# Sec_Controller_Sheet4.net
KiCad netlist of a schematic drawn in Altium Designer
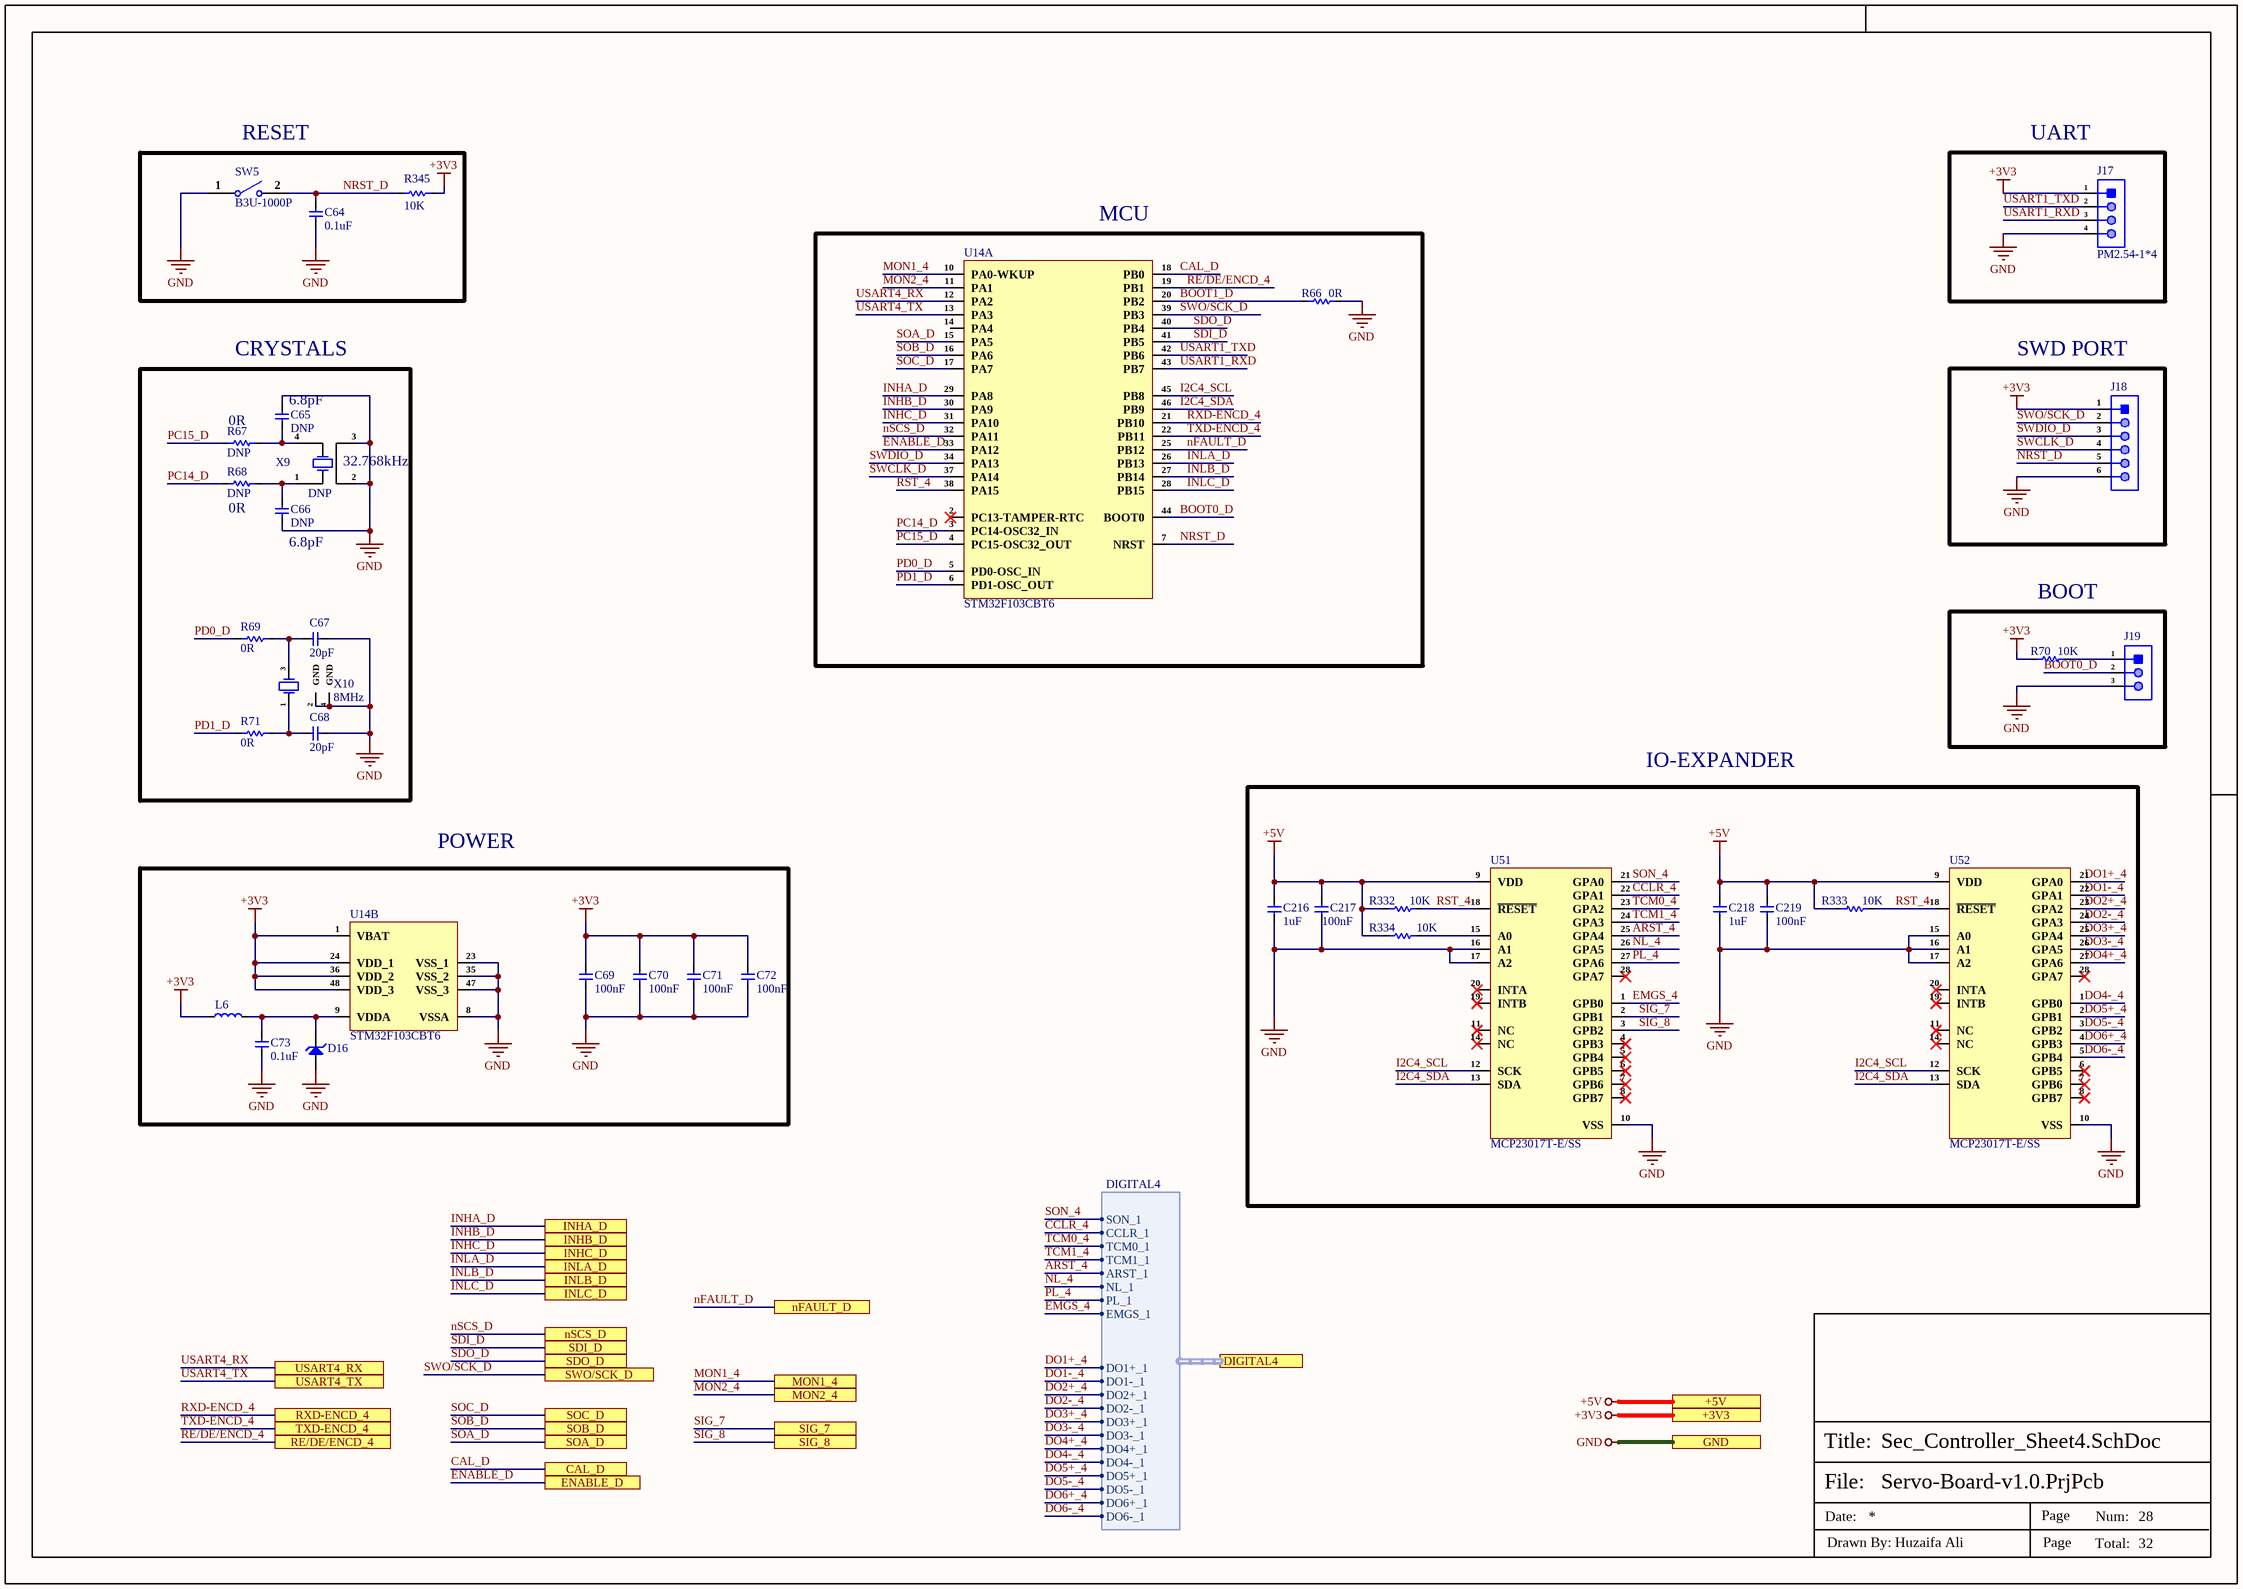
[diagram p0: Sec_Controller_Sheet4.SchDoc]

(export (version "E")
  (design (tool "Eeschema 10.0.6"))
  (components
    (comp (ref "C64")
      (value "0.1uF")
      (footprint "Cap-0402")
      (description "CAP CER 0.1UF 16V X7R 0402")
      (fields
        (field (name "MANUFACTURER") "Yageo")
        (field (name "MANUFACTURER PART NUMBER") "CC0402JRX7R7BB104")
      )
      (libsource (lib "eSpark Libraries") (part "CC0402JRX7R7BB104"))
    )
    (comp (ref "C65")
      (value "DNP")
      (footprint "Cap-0402")
      (description "CAP CER 6.8PF 50V C0G/NPO 0402")
      (fields
        (field (name "MANUFACTURER") "Yageo")
        (field (name "MANUFACTURER PART NUMBER") "CC0402CRNPO9BN6R8")
      )
      (libsource (lib "eSpark Libraries") (part "CC0402CRNPO9BN6R8"))
    )
    (comp (ref "C66")
      (value "DNP")
      (footprint "Cap-0402")
      (description "CAP CER 6.8PF 50V C0G/NPO 0402")
      (fields
        (field (name "MANUFACTURER") "Yageo")
        (field (name "MANUFACTURER PART NUMBER") "CC0402CRNPO9BN6R8")
      )
      (libsource (lib "eSpark Libraries") (part "CC0402CRNPO9BN6R8"))
    )
    (comp (ref "C67")
      (value "20pF")
      (footprint "Cap-0402")
      (description "CAP CER 20PF 50V C0G/NPO 0402")
      (fields (field (name "LCSC PART NUMBER") "C107000") (field (name "MANUFACTURER") "Yageo"))
      (libsource (lib "eSpark Libraries") (part "CC0402JRNPO9BN200"))
    )
    (comp (ref "C68")
      (value "20pF")
      (footprint "Cap-0402")
      (description "CAP CER 20PF 50V C0G/NPO 0402")
      (fields (field (name "LCSC PART NUMBER") "C107000") (field (name "MANUFACTURER") "Yageo"))
      (libsource (lib "eSpark Libraries") (part "CC0402JRNPO9BN200"))
    )
    (comp (ref "C69")
      (value "100nF")
      (footprint "cap-0402")
      (description "CAP CER 0.1UF 50V X7R 0402")
      (fields
        (field (name "MANUFACTURER") "TDK")
        (field (name "MANUFACTURER PART NUMBER") "C1005X7R1H104KT000F")
      )
      (libsource (lib "eSpark Libraries") (part "C1005X7R1H104KT000F"))
    )
    (comp (ref "C70")
      (value "100nF")
      (footprint "cap-0402")
      (description "CAP CER 0.1UF 50V X7R 0402")
      (fields
        (field (name "MANUFACTURER") "TDK")
        (field (name "MANUFACTURER PART NUMBER") "C1005X7R1H104KT000F")
      )
      (libsource (lib "eSpark Libraries") (part "C1005X7R1H104KT000F"))
    )
    (comp (ref "C71")
      (value "100nF")
      (footprint "cap-0402")
      (description "CAP CER 0.1UF 50V X7R 0402")
      (fields
        (field (name "MANUFACTURER") "TDK")
        (field (name "MANUFACTURER PART NUMBER") "C1005X7R1H104KT000F")
      )
      (libsource (lib "eSpark Libraries") (part "C1005X7R1H104KT000F"))
    )
    (comp (ref "C72")
      (value "100nF")
      (footprint "cap-0402")
      (description "CAP CER 0.1UF 50V X7R 0402")
      (fields
        (field (name "MANUFACTURER") "TDK")
        (field (name "MANUFACTURER PART NUMBER") "C1005X7R1H104KT000F")
      )
      (libsource (lib "eSpark Libraries") (part "C1005X7R1H104KT000F"))
    )
    (comp (ref "C73")
      (value "0.1uF")
      (footprint "Cap-0402")
      (description "CAP CER 0.1UF 16V X7R 0402")
      (fields
        (field (name "MANUFACTURER") "Yageo")
        (field (name "MANUFACTURER PART NUMBER") "CC0402JRX7R7BB104")
      )
      (libsource (lib "eSpark Libraries") (part "CC0402JRX7R7BB104"))
    )
    (comp (ref "C216")
      (value "1uF")
      (footprint "Cap-0402")
      (description "CAP CER 1UF 10V X5R 0402")
      (fields
        (field (name "MANUFACTURER") "Yageo")
        (field (name "MANUFACTURER PART NUMBER") "CC0402KRX5R6BB105")
      )
      (libsource (lib "eSpark Libraries") (part "CC0402KRX5R6BB105"))
    )
    (comp (ref "C217")
      (value "100nF")
      (footprint "cap-0402")
      (description "CAP CER 0.1UF 50V X7R 0402")
      (fields
        (field (name "MANUFACTURER") "TDK")
        (field (name "MANUFACTURER PART NUMBER") "C1005X7R1H104KT000F")
      )
      (libsource (lib "eSpark Libraries") (part "C1005X7R1H104KT000F"))
    )
    (comp (ref "C218")
      (value "1uF")
      (footprint "Cap-0402")
      (description "CAP CER 1UF 10V X5R 0402")
      (fields
        (field (name "MANUFACTURER") "Yageo")
        (field (name "MANUFACTURER PART NUMBER") "CC0402KRX5R6BB105")
      )
      (libsource (lib "eSpark Libraries") (part "CC0402KRX5R6BB105"))
    )
    (comp (ref "C219")
      (value "100nF")
      (footprint "cap-0402")
      (description "CAP CER 0.1UF 50V X7R 0402")
      (fields
        (field (name "MANUFACTURER") "TDK")
        (field (name "MANUFACTURER PART NUMBER") "C1005X7R1H104KT000F")
      )
      (libsource (lib "eSpark Libraries") (part "C1005X7R1H104KT000F"))
    )
    (comp (ref "D16")
      (value "AZ3003-01G")
      (footprint "SOD-123")
      (description "TVS SURGE PROTECTOR 1-CH 3.3V")
      (fields (field (name "MANUFACTURER") "Amazing"))
      (libsource (lib "eSpark Libraries") (part "AZ3003-01G"))
    )
    (comp (ref "J17")
      (value "PM2.54-1*4")
      (footprint "HDR1X4 Female")
      (fields (field (name "MANUFACTURER") "ZHOURI") (field (name "LCSC PART NUMBER") "C5116530"))
      (libsource (lib "eSpark Libraries") (part "PM2.54-1*4"))
    )
    (comp (ref "J18")
      (value "X6511WV-06H-C60D30")
      (footprint "HDR1X6_")
      (fields (field (name "MANUFACTURER") "XKB") (field (name "LCSC PART NUMBER") "C706878"))
      (libsource (lib "eSpark Libraries") (part "X6511WV-06H-C60D30"))
    )
    (comp (ref "J19")
      (value "68000-103HLF")
      (footprint "HDR1X3_")
      (description "CONN HEADER VERT 3POS 2.54MM")
      (fields (field (name "LCSC PART NUMBER") "C168677"))
      (libsource (lib "eSpark Libraries") (part "68000-103HLF"))
    )
    (comp (ref "L6")
      (value "BLM15AG601SN1D")
      (footprint "IND-0402")
      (description "FERRITE BEAD 600 OHM 0402 1LN")
      (fields (field (name "MANUFACTURER") "Murata") (field (name "TOLERANCE") "25%"))
      (libsource (lib "eSpark Libraries") (part "BLM15AG601SN1D"))
    )
    (comp (ref "R66")
      (value "0R")
      (footprint "Res-0402")
      (description "RES 0 OHM JUMPER 1/16W 0402")
      (fields
        (field (name "MANUFACTURER") "Yageo")
        (field (name "MANUFACTURER PART NUMBER") "RC0402FR-070RL")
      )
      (libsource (lib "eSpark Libraries") (part "RC0402FR-070RL"))
    )
    (comp (ref "R67")
      (value "DNP")
      (footprint "Res-0603")
      (description "RES 0 OHM JUMPER 1/10W 0603")
      (fields
        (field (name "MANUFACTURER") "Yageo")
        (field (name "MANUFACTURER PART NUMBER") "RC0603JR-070RL")
      )
      (libsource (lib "eSpark Libraries") (part "RC0603JR-070RL"))
    )
    (comp (ref "R68")
      (value "DNP")
      (footprint "Res-0603")
      (description "RES 0 OHM JUMPER 1/10W 0603")
      (fields
        (field (name "MANUFACTURER") "Yageo")
        (field (name "MANUFACTURER PART NUMBER") "RC0603JR-070RL")
      )
      (libsource (lib "eSpark Libraries") (part "RC0603JR-070RL"))
    )
    (comp (ref "R69")
      (value "0R")
      (footprint "Res-0603")
      (description "RES 0 OHM JUMPER 1/10W 0603")
      (fields
        (field (name "MANUFACTURER") "Yageo")
        (field (name "MANUFACTURER PART NUMBER") "RC0603JR-070RL")
      )
      (libsource (lib "eSpark Libraries") (part "RC0603JR-070RL"))
    )
    (comp (ref "R70")
      (value "10K")
      (footprint "Res-0402")
      (description "RES 10K OHM 1% 1/16W 0402")
      (fields
        (field (name "MANUFACTURER") "Yageo")
        (field (name "MANUFACTURER PART NUMBER") "RC0402FR-0710KL")
      )
      (libsource (lib "eSpark Libraries") (part "RC0402FR-0710KL"))
    )
    (comp (ref "R71")
      (value "0R")
      (footprint "Res-0603")
      (description "RES 0 OHM JUMPER 1/10W 0603")
      (fields
        (field (name "MANUFACTURER") "Yageo")
        (field (name "MANUFACTURER PART NUMBER") "RC0603JR-070RL")
      )
      (libsource (lib "eSpark Libraries") (part "RC0603JR-070RL"))
    )
    (comp (ref "R332")
      (value "10K")
      (footprint "Res-0402")
      (description "RES 10K OHM 1% 1/16W 0402")
      (fields
        (field (name "MANUFACTURER") "Yageo")
        (field (name "MANUFACTURER PART NUMBER") "RC0402FR-0710KL")
      )
      (libsource (lib "eSpark Libraries") (part "RC0402FR-0710KL"))
    )
    (comp (ref "R333")
      (value "10K")
      (footprint "Res-0402")
      (description "RES 10K OHM 1% 1/16W 0402")
      (fields
        (field (name "MANUFACTURER") "Yageo")
        (field (name "MANUFACTURER PART NUMBER") "RC0402FR-0710KL")
      )
      (libsource (lib "eSpark Libraries") (part "RC0402FR-0710KL"))
    )
    (comp (ref "R334")
      (value "10K")
      (footprint "Res-0402")
      (description "RES 10K OHM 1% 1/16W 0402")
      (fields
        (field (name "MANUFACTURER") "Yageo")
        (field (name "MANUFACTURER PART NUMBER") "RC0402FR-0710KL")
      )
      (libsource (lib "eSpark Libraries") (part "RC0402FR-0710KL"))
    )
    (comp (ref "R345")
      (value "10K")
      (footprint "Res-0402")
      (description "RES 10K OHM 1% 1/16W 0402")
      (fields
        (field (name "MANUFACTURER") "Yageo")
        (field (name "MANUFACTURER PART NUMBER") "RC0402FR-0710KL")
      )
      (libsource (lib "eSpark Libraries") (part "RC0402FR-0710KL"))
    )
    (comp (ref "SW5")
      (value "B3U-1000P")
      (footprint "B3U-1000P")
      (description "SWITCH TACTILE SPST-NO 0.05A 12V")
      (fields (field (name "MANUFACTURER") "Omron") (field (name "LCSC PART NUMBER") "C231329"))
      (libsource (lib "eSpark Libraries") (part "B3U-1000P"))
    )
    (comp (ref "U14")
      (value "STM32F103CBT6")
      (footprint "48-LQFP (7x7)_")
      (description "IC MCU 32BIT 128KB FLASH 48LQFP")
      (fields (field (name "MANUFACTURER") "STMicroelectronics") (field (name "LCSC PART NUMBER") "C8304"))
      (libsource (lib "eSpark Libraries") (part "STM32F103CBT6"))
    )
    (comp (ref "U51")
      (value "MCP23017T-E/SS")
      (footprint "SSOP-28-208mil")
      (description "IC XPNDR 1.7MHZ I2C 28SSOP")
      (fields (field (name "MANUFACTURER") "Microchip") (field (name "LCSC PART NUMBER") "C558584"))
      (libsource (lib "eSpark Libraries") (part "MCP23017T-E/SS"))
    )
    (comp (ref "U52")
      (value "MCP23017T-E/SS")
      (footprint "SSOP-28-208mil")
      (description "IC XPNDR 1.7MHZ I2C 28SSOP")
      (fields (field (name "MANUFACTURER") "Microchip") (field (name "LCSC PART NUMBER") "C558584"))
      (libsource (lib "eSpark Libraries") (part "MCP23017T-E/SS"))
    )
    (comp (ref "X9")
      (value "DNP")
      (footprint "MC-306")
      (description "32.768kHz 12.5pF ±20ppm MC-306 Crystals ROHS")
      (fields
        (field (name "MANUFACTURER") "Seiko Epson")
        (field (name "MANUFACTURER PART NUMBER") "MC-306 32.7680K-A0:ROHS")
      )
      (libsource (lib "eSpark Libraries") (part "MC-306 32.7680K-A0{colon}ROHS"))
    )
    (comp (ref "X10")
      (value "8MHz")
      (footprint "5TJ480000XYLBC_")
      (description "8MHz 18pF ±10ppm SMD5032-4P Crystals ROHS")
      (fields (field (name "MANUFACTURER") "JYJE") (field (name "MANUFACTURER PART NUMBER") "5TJ480000XYLBC"))
      (libsource (lib "eSpark Libraries") (part "5TJ480000XYLBC"))
    )
  )
  (nets
    (net (code "2") (name "+3V3") (class "Default")
      (node (ref "C69") (pin "2") (pinfunction "2_2") (pintype "passive"))
      (node (ref "C70") (pin "2") (pinfunction "2_2") (pintype "passive"))
      (node (ref "C71") (pin "2") (pinfunction "2_2") (pintype "passive"))
      (node (ref "C72") (pin "2") (pinfunction "2_2") (pintype "passive"))
      (node (ref "J17") (pin "1") (pinfunction "1_1") (pintype "passive"))
      (node (ref "J18") (pin "1") (pinfunction "1_1") (pintype "passive"))
      (node (ref "L6") (pin "1") (pinfunction "1_1") (pintype "passive"))
      (node (ref "R345") (pin "2") (pinfunction "2_2") (pintype "passive"))
      (node (ref "R70") (pin "2") (pinfunction "2_2") (pintype "passive"))
      (node (ref "U14") (pin "1") (pinfunction "VBAT_1") (pintype "power_in"))
      (node (ref "U14") (pin "24") (pinfunction "VDD_1_24") (pintype "power_in"))
      (node (ref "U14") (pin "36") (pinfunction "VDD_2_36") (pintype "power_in"))
      (node (ref "U14") (pin "48") (pinfunction "VDD_3_48") (pintype "power_in"))
    )
    (net (code "3") (name "+5V") (class "Default")
      (node (ref "C216") (pin "2") (pinfunction "2_2") (pintype "passive"))
      (node (ref "C217") (pin "2") (pinfunction "2_2") (pintype "passive"))
      (node (ref "C218") (pin "2") (pinfunction "2_2") (pintype "passive"))
      (node (ref "C219") (pin "2") (pinfunction "2_2") (pintype "passive"))
      (node (ref "R332") (pin "2") (pinfunction "2_2") (pintype "passive"))
      (node (ref "R333") (pin "2") (pinfunction "2_2") (pintype "passive"))
      (node (ref "R334") (pin "2") (pinfunction "2_2") (pintype "passive"))
      (node (ref "U51") (pin "9") (pinfunction "VDD_9") (pintype "passive"))
      (node (ref "U52") (pin "9") (pinfunction "VDD_9") (pintype "passive"))
    )
    (net (code "4") (name "/ARST_4") (class "Default")
      (node (ref "U51") (pin "25") (pinfunction "GPA4_25") (pintype "passive"))
    )
    (net (code "5") (name "/BOOT0_D") (class "Default")
      (node (ref "J19") (pin "2") (pinfunction "2_2") (pintype "passive"))
      (node (ref "U14") (pin "44") (pinfunction "BOOT0_44") (pintype "passive"))
    )
    (net (code "6") (name "/BOOT1_D") (class "Default")
      (node (ref "R66") (pin "1") (pinfunction "1_1") (pintype "passive"))
      (node (ref "U14") (pin "20") (pinfunction "PB2_20") (pintype "passive"))
    )
    (net (code "7") (name "/CAL_D") (class "Default")
      (node (ref "U14") (pin "18") (pinfunction "PB0_18") (pintype "passive"))
    )
    (net (code "8") (name "/CCLR_4") (class "Default")
      (node (ref "U51") (pin "22") (pinfunction "GPA1_22") (pintype "passive"))
    )
    (net (code "9") (name "/DO1+_4") (class "Default")
      (node (ref "U52") (pin "21") (pinfunction "GPA0_21") (pintype "passive"))
    )
    (net (code "10") (name "/DO1-_4") (class "Default")
      (node (ref "U52") (pin "22") (pinfunction "GPA1_22") (pintype "passive"))
    )
    (net (code "11") (name "/DO2+_4") (class "Default")
      (node (ref "U52") (pin "23") (pinfunction "GPA2_23") (pintype "passive"))
    )
    (net (code "12") (name "/DO2-_4") (class "Default")
      (node (ref "U52") (pin "24") (pinfunction "GPA3_24") (pintype "passive"))
    )
    (net (code "13") (name "/DO3+_4") (class "Default")
      (node (ref "U52") (pin "25") (pinfunction "GPA4_25") (pintype "passive"))
    )
    (net (code "14") (name "/DO3-_4") (class "Default")
      (node (ref "U52") (pin "26") (pinfunction "GPA5_26") (pintype "passive"))
    )
    (net (code "15") (name "/DO4+_4") (class "Default")
      (node (ref "U52") (pin "27") (pinfunction "GPA6_27") (pintype "passive"))
    )
    (net (code "16") (name "/DO4-_4") (class "Default")
      (node (ref "U52") (pin "1") (pinfunction "GPB0_1") (pintype "passive"))
    )
    (net (code "17") (name "/DO5+_4") (class "Default")
      (node (ref "U52") (pin "2") (pinfunction "GPB1_2") (pintype "passive"))
    )
    (net (code "18") (name "/DO5-_4") (class "Default")
      (node (ref "U52") (pin "3") (pinfunction "GPB2_3") (pintype "passive"))
    )
    (net (code "19") (name "/DO6+_4") (class "Default")
      (node (ref "U52") (pin "4") (pinfunction "GPB3_4") (pintype "passive"))
    )
    (net (code "20") (name "/DO6-_4") (class "Default")
      (node (ref "U52") (pin "5") (pinfunction "GPB4_5") (pintype "passive"))
    )
    (net (code "21") (name "/EMGS_4") (class "Default")
      (node (ref "U51") (pin "1") (pinfunction "GPB0_1") (pintype "passive"))
    )
    (net (code "22") (name "/ENABLE_D") (class "Default")
      (node (ref "U14") (pin "33") (pinfunction "PA12_33") (pintype "passive"))
    )
    (net (code "23") (name "/I2C4_SCL") (class "Default")
      (node (ref "U14") (pin "45") (pinfunction "PB8_45") (pintype "passive"))
      (node (ref "U51") (pin "12") (pinfunction "SCK_12") (pintype "passive"))
      (node (ref "U52") (pin "12") (pinfunction "SCK_12") (pintype "passive"))
    )
    (net (code "24") (name "/I2C4_SDA") (class "Default")
      (node (ref "U14") (pin "46") (pinfunction "PB9_46") (pintype "passive"))
      (node (ref "U51") (pin "13") (pinfunction "SDA_13") (pintype "passive"))
      (node (ref "U52") (pin "13") (pinfunction "SDA_13") (pintype "passive"))
    )
    (net (code "25") (name "/INHA_D") (class "Default")
      (node (ref "U14") (pin "29") (pinfunction "PA8_29") (pintype "passive"))
    )
    (net (code "26") (name "/INHB_D") (class "Default")
      (node (ref "U14") (pin "30") (pinfunction "PA9_30") (pintype "passive"))
    )
    (net (code "27") (name "/INHC_D") (class "Default")
      (node (ref "U14") (pin "31") (pinfunction "PA10_31") (pintype "passive"))
    )
    (net (code "28") (name "/INLA_D") (class "Default")
      (node (ref "U14") (pin "26") (pinfunction "PB13_26") (pintype "passive"))
    )
    (net (code "29") (name "/INLB_D") (class "Default")
      (node (ref "U14") (pin "27") (pinfunction "PB14_27") (pintype "passive"))
    )
    (net (code "30") (name "/INLC_D") (class "Default")
      (node (ref "U14") (pin "28") (pinfunction "PB15_28") (pintype "passive"))
    )
    (net (code "31") (name "/MON1_4") (class "Default")
      (node (ref "U14") (pin "10") (pinfunction "PA0-WKUP_10") (pintype "passive"))
    )
    (net (code "32") (name "/MON2_4") (class "Default")
      (node (ref "U14") (pin "11") (pinfunction "PA1_11") (pintype "passive"))
    )
    (net (code "33") (name "/NL_4") (class "Default")
      (node (ref "U51") (pin "26") (pinfunction "GPA5_26") (pintype "passive"))
    )
    (net (code "34") (name "/NRST_D") (class "Default")
      (node (ref "C64") (pin "2") (pinfunction "2_2") (pintype "passive"))
      (node (ref "J18") (pin "5") (pinfunction "5_5") (pintype "passive"))
      (node (ref "R345") (pin "1") (pinfunction "1_1") (pintype "passive"))
      (node (ref "SW5") (pin "2") (pinfunction "2_2") (pintype "passive"))
      (node (ref "U14") (pin "7") (pinfunction "NRST_7") (pintype "passive"))
    )
    (net (code "35") (name "/PC14_D") (class "Default")
      (node (ref "R68") (pin "2") (pinfunction "2_2") (pintype "passive"))
      (node (ref "U14") (pin "3") (pinfunction "PC14-OSC32_IN_3") (pintype "passive"))
    )
    (net (code "36") (name "/PC15_D") (class "Default")
      (node (ref "R67") (pin "2") (pinfunction "2_2") (pintype "passive"))
      (node (ref "U14") (pin "4") (pinfunction "PC15-OSC32_OUT_4") (pintype "passive"))
    )
    (net (code "37") (name "/PD0_D") (class "Default")
      (node (ref "R69") (pin "2") (pinfunction "2_2") (pintype "passive"))
      (node (ref "U14") (pin "5") (pinfunction "PD0-OSC_IN_5") (pintype "passive"))
    )
    (net (code "38") (name "/PD1_D") (class "Default")
      (node (ref "R71") (pin "2") (pinfunction "2_2") (pintype "passive"))
      (node (ref "U14") (pin "6") (pinfunction "PD1-OSC_OUT_6") (pintype "passive"))
    )
    (net (code "39") (name "/PL_4") (class "Default")
      (node (ref "U51") (pin "27") (pinfunction "GPA6_27") (pintype "passive"))
    )
    (net (code "40") (name "/RE{slash}DE{slash}ENCD_4") (class "Default")
      (node (ref "U14") (pin "19") (pinfunction "PB1_19") (pintype "passive"))
    )
    (net (code "41") (name "/RST_4") (class "Default")
      (node (ref "R332") (pin "1") (pinfunction "1_1") (pintype "passive"))
      (node (ref "R333") (pin "1") (pinfunction "1_1") (pintype "passive"))
      (node (ref "U14") (pin "38") (pinfunction "PA15_38") (pintype "passive"))
      (node (ref "U51") (pin "18") (pinfunction "~{RESET}_18") (pintype "passive"))
      (node (ref "U52") (pin "18") (pinfunction "~{RESET}_18") (pintype "passive"))
    )
    (net (code "42") (name "/RXD-ENCD_4") (class "Default")
      (node (ref "U14") (pin "21") (pinfunction "PB10_21") (pintype "passive"))
    )
    (net (code "43") (name "/SDI_D") (class "Default")
      (node (ref "U14") (pin "41") (pinfunction "PB5_41") (pintype "passive"))
    )
    (net (code "44") (name "/SDO_D") (class "Default")
      (node (ref "U14") (pin "40") (pinfunction "PB4_40") (pintype "passive"))
    )
    (net (code "45") (name "/SIG_7") (class "Default")
      (node (ref "U51") (pin "2") (pinfunction "GPB1_2") (pintype "passive"))
    )
    (net (code "46") (name "/SIG_8") (class "Default")
      (node (ref "U51") (pin "3") (pinfunction "GPB2_3") (pintype "passive"))
    )
    (net (code "47") (name "/SOA_D") (class "Default")
      (node (ref "U14") (pin "15") (pinfunction "PA5_15") (pintype "passive"))
    )
    (net (code "48") (name "/SOB_D") (class "Default")
      (node (ref "U14") (pin "16") (pinfunction "PA6_16") (pintype "passive"))
    )
    (net (code "49") (name "/SOC_D") (class "Default")
      (node (ref "U14") (pin "17") (pinfunction "PA7_17") (pintype "passive"))
    )
    (net (code "50") (name "/SON_4") (class "Default")
      (node (ref "U51") (pin "21") (pinfunction "GPA0_21") (pintype "passive"))
    )
    (net (code "51") (name "/SWCLK_D") (class "Default")
      (node (ref "J18") (pin "4") (pinfunction "4_4") (pintype "passive"))
      (node (ref "U14") (pin "37") (pinfunction "PA14_37") (pintype "passive"))
    )
    (net (code "52") (name "/SWDIO_D") (class "Default")
      (node (ref "J18") (pin "3") (pinfunction "3_3") (pintype "passive"))
      (node (ref "U14") (pin "34") (pinfunction "PA13_34") (pintype "passive"))
    )
    (net (code "53") (name "/SWO{slash}SCK_D") (class "Default")
      (node (ref "J18") (pin "2") (pinfunction "2_2") (pintype "passive"))
      (node (ref "U14") (pin "39") (pinfunction "PB3_39") (pintype "passive"))
    )
    (net (code "54") (name "/TCM0_4") (class "Default")
      (node (ref "U51") (pin "23") (pinfunction "GPA2_23") (pintype "passive"))
    )
    (net (code "55") (name "/TCM1_4") (class "Default")
      (node (ref "U51") (pin "24") (pinfunction "GPA3_24") (pintype "passive"))
    )
    (net (code "56") (name "/TXD-ENCD_4") (class "Default")
      (node (ref "U14") (pin "22") (pinfunction "PB11_22") (pintype "passive"))
    )
    (net (code "57") (name "/USART1_RXD") (class "Default")
      (node (ref "J17") (pin "3") (pinfunction "3_3") (pintype "passive"))
      (node (ref "U14") (pin "43") (pinfunction "PB7_43") (pintype "passive"))
    )
    (net (code "58") (name "/USART1_TXD") (class "Default")
      (node (ref "J17") (pin "2") (pinfunction "2_2") (pintype "passive"))
      (node (ref "U14") (pin "42") (pinfunction "PB6_42") (pintype "passive"))
    )
    (net (code "59") (name "/USART4_RX") (class "Default")
      (node (ref "U14") (pin "12") (pinfunction "PA2_12") (pintype "passive"))
    )
    (net (code "60") (name "/USART4_TX") (class "Default")
      (node (ref "U14") (pin "13") (pinfunction "PA3_13") (pintype "passive"))
    )
    (net (code "61") (name "/nFAULT_D") (class "Default")
      (node (ref "U14") (pin "25") (pinfunction "PB12_25") (pintype "passive"))
    )
    (net (code "62") (name "/nSCS_D") (class "Default")
      (node (ref "U14") (pin "32") (pinfunction "PA11_32") (pintype "passive"))
    )
    (net (code "64") (name "GND") (class "Default")
      (node (ref "C216") (pin "1") (pinfunction "1_1") (pintype "passive"))
      (node (ref "C217") (pin "1") (pinfunction "1_1") (pintype "passive"))
      (node (ref "C218") (pin "1") (pinfunction "1_1") (pintype "passive"))
      (node (ref "C219") (pin "1") (pinfunction "1_1") (pintype "passive"))
      (node (ref "C64") (pin "1") (pinfunction "1_1") (pintype "passive"))
      (node (ref "C65") (pin "2") (pinfunction "2_2") (pintype "passive"))
      (node (ref "C66") (pin "1") (pinfunction "1_1") (pintype "passive"))
      (node (ref "C67") (pin "2") (pinfunction "2_2") (pintype "passive"))
      (node (ref "C68") (pin "2") (pinfunction "2_2") (pintype "passive"))
      (node (ref "C69") (pin "1") (pinfunction "1_1") (pintype "passive"))
      (node (ref "C70") (pin "1") (pinfunction "1_1") (pintype "passive"))
      (node (ref "C71") (pin "1") (pinfunction "1_1") (pintype "passive"))
      (node (ref "C72") (pin "1") (pinfunction "1_1") (pintype "passive"))
      (node (ref "C73") (pin "1") (pinfunction "1_1") (pintype "passive"))
      (node (ref "D16") (pin "1") (pinfunction "A_1") (pintype "passive"))
      (node (ref "J17") (pin "4") (pinfunction "4_4") (pintype "passive"))
      (node (ref "J18") (pin "6") (pinfunction "6_6") (pintype "passive"))
      (node (ref "J19") (pin "3") (pinfunction "3_3") (pintype "passive"))
      (node (ref "R66") (pin "2") (pinfunction "2_2") (pintype "passive"))
      (node (ref "SW5") (pin "1") (pinfunction "1_1") (pintype "passive"))
      (node (ref "U14") (pin "23") (pinfunction "VSS_1_23") (pintype "power_in"))
      (node (ref "U14") (pin "35") (pinfunction "VSS_2_35") (pintype "power_in"))
      (node (ref "U14") (pin "47") (pinfunction "VSS_3_47") (pintype "power_in"))
      (node (ref "U14") (pin "8") (pinfunction "VSSA_8") (pintype "power_in"))
      (node (ref "U51") (pin "10") (pinfunction "VSS_10") (pintype "passive"))
      (node (ref "U51") (pin "16") (pinfunction "A1_16") (pintype "passive"))
      (node (ref "U51") (pin "17") (pinfunction "A2_17") (pintype "passive"))
      (node (ref "U52") (pin "10") (pinfunction "VSS_10") (pintype "passive"))
      (node (ref "U52") (pin "15") (pinfunction "A0_15") (pintype "passive"))
      (node (ref "U52") (pin "16") (pinfunction "A1_16") (pintype "passive"))
      (node (ref "U52") (pin "17") (pinfunction "A2_17") (pintype "passive"))
      (node (ref "X10") (pin "2") (pinfunction "GND_2") (pintype "passive"))
      (node (ref "X10") (pin "4") (pinfunction "GND_4") (pintype "passive"))
      (node (ref "X9") (pin "2") (pinfunction "2_2") (pintype "passive"))
      (node (ref "X9") (pin "3") (pinfunction "3_3") (pintype "passive"))
    )
    (net (code "65") (name "Net-(D16-K)") (class "Default")
      (node (ref "C73") (pin "2") (pinfunction "2_2") (pintype "passive"))
      (node (ref "D16") (pin "2") (pinfunction "K_2") (pintype "passive"))
      (node (ref "L6") (pin "2") (pinfunction "2_2") (pintype "passive"))
      (node (ref "U14") (pin "9") (pinfunction "VDDA_9") (pintype "power_in"))
    )
    (net (code "66") (name "Net-(J19-Pad1)") (class "Default")
      (node (ref "J19") (pin "1") (pinfunction "1_1") (pintype "passive"))
      (node (ref "R70") (pin "1") (pinfunction "1_1") (pintype "passive"))
    )
    (net (code "67") (name "Net-(U51-A0)") (class "Default")
      (node (ref "R334") (pin "1") (pinfunction "1_1") (pintype "passive"))
      (node (ref "U51") (pin "15") (pinfunction "A0_15") (pintype "passive"))
    )
    (net (code "68") (name "Net-(X9-OSC1)") (class "Default")
      (node (ref "C66") (pin "2") (pinfunction "2_2") (pintype "passive"))
      (node (ref "R68") (pin "1") (pinfunction "1_1") (pintype "passive"))
      (node (ref "X9") (pin "1") (pinfunction "OSC1_1") (pintype "passive"))
    )
    (net (code "69") (name "Net-(X9-OSC2)") (class "Default")
      (node (ref "C65") (pin "1") (pinfunction "1_1") (pintype "passive"))
      (node (ref "R67") (pin "1") (pinfunction "1_1") (pintype "passive"))
      (node (ref "X9") (pin "4") (pinfunction "OSC2_4") (pintype "passive"))
    )
    (net (code "70") (name "Net-(X10-OSC1)") (class "Default")
      (node (ref "C68") (pin "1") (pinfunction "1_1") (pintype "passive"))
      (node (ref "R71") (pin "1") (pinfunction "1_1") (pintype "passive"))
      (node (ref "X10") (pin "1") (pinfunction "OSC1_1") (pintype "passive"))
    )
    (net (code "71") (name "Net-(X10-OSC2)") (class "Default")
      (node (ref "C67") (pin "1") (pinfunction "1_1") (pintype "passive"))
      (node (ref "R69") (pin "1") (pinfunction "1_1") (pintype "passive"))
      (node (ref "X10") (pin "3") (pinfunction "OSC2_3") (pintype "passive"))
    )
    (net (code "72") (name "unconnected-(U14A-PA4-Pad14)") (class "Default")
      (node (ref "U14") (pin "14") (pinfunction "PA4_14") (pintype "passive"))
    )
    (net (code "73") (name "unconnected-(U14A-PC13-TAMPER-RTC-Pad2)") (class "Default")
      (node (ref "U14") (pin "2") (pinfunction "PC13-TAMPER-RTC_2") (pintype "passive+no_connect"))
    )
    (net (code "74") (name "unconnected-(U51-GPA7-Pad28)") (class "Default")
      (node (ref "U51") (pin "28") (pinfunction "GPA7_28") (pintype "passive+no_connect"))
    )
    (net (code "75") (name "unconnected-(U51-GPB3-Pad4)") (class "Default")
      (node (ref "U51") (pin "4") (pinfunction "GPB3_4") (pintype "passive+no_connect"))
    )
    (net (code "76") (name "unconnected-(U51-GPB4-Pad5)") (class "Default")
      (node (ref "U51") (pin "5") (pinfunction "GPB4_5") (pintype "passive+no_connect"))
    )
    (net (code "77") (name "unconnected-(U51-GPB5-Pad6)") (class "Default")
      (node (ref "U51") (pin "6") (pinfunction "GPB5_6") (pintype "passive+no_connect"))
    )
    (net (code "78") (name "unconnected-(U51-GPB6-Pad7)") (class "Default")
      (node (ref "U51") (pin "7") (pinfunction "GPB6_7") (pintype "passive+no_connect"))
    )
    (net (code "79") (name "unconnected-(U51-GPB7-Pad8)") (class "Default")
      (node (ref "U51") (pin "8") (pinfunction "GPB7_8") (pintype "passive+no_connect"))
    )
    (net (code "80") (name "unconnected-(U51-INTA-Pad20)") (class "Default")
      (node (ref "U51") (pin "20") (pinfunction "INTA_20") (pintype "passive+no_connect"))
    )
    (net (code "81") (name "unconnected-(U51-INTB-Pad19)") (class "Default")
      (node (ref "U51") (pin "19") (pinfunction "INTB_19") (pintype "passive+no_connect"))
    )
    (net (code "82") (name "unconnected-(U51-NC-Pad11)") (class "Default")
      (node (ref "U51") (pin "11") (pinfunction "NC_11") (pintype "passive+no_connect"))
    )
    (net (code "83") (name "unconnected-(U51-NC-Pad14)") (class "Default")
      (node (ref "U51") (pin "14") (pinfunction "NC_14") (pintype "passive+no_connect"))
    )
    (net (code "84") (name "unconnected-(U52-GPA7-Pad28)") (class "Default")
      (node (ref "U52") (pin "28") (pinfunction "GPA7_28") (pintype "passive+no_connect"))
    )
    (net (code "85") (name "unconnected-(U52-GPB5-Pad6)") (class "Default")
      (node (ref "U52") (pin "6") (pinfunction "GPB5_6") (pintype "passive+no_connect"))
    )
    (net (code "86") (name "unconnected-(U52-GPB6-Pad7)") (class "Default")
      (node (ref "U52") (pin "7") (pinfunction "GPB6_7") (pintype "passive+no_connect"))
    )
    (net (code "87") (name "unconnected-(U52-GPB7-Pad8)") (class "Default")
      (node (ref "U52") (pin "8") (pinfunction "GPB7_8") (pintype "passive+no_connect"))
    )
    (net (code "88") (name "unconnected-(U52-INTA-Pad20)") (class "Default")
      (node (ref "U52") (pin "20") (pinfunction "INTA_20") (pintype "passive+no_connect"))
    )
    (net (code "89") (name "unconnected-(U52-INTB-Pad19)") (class "Default")
      (node (ref "U52") (pin "19") (pinfunction "INTB_19") (pintype "passive+no_connect"))
    )
    (net (code "90") (name "unconnected-(U52-NC-Pad11)") (class "Default")
      (node (ref "U52") (pin "11") (pinfunction "NC_11") (pintype "passive+no_connect"))
    )
    (net (code "91") (name "unconnected-(U52-NC-Pad14)") (class "Default")
      (node (ref "U52") (pin "14") (pinfunction "NC_14") (pintype "passive+no_connect"))
    )
  )
)
